# MCU.net
KiCad netlist of a schematic drawn in Altium Designer
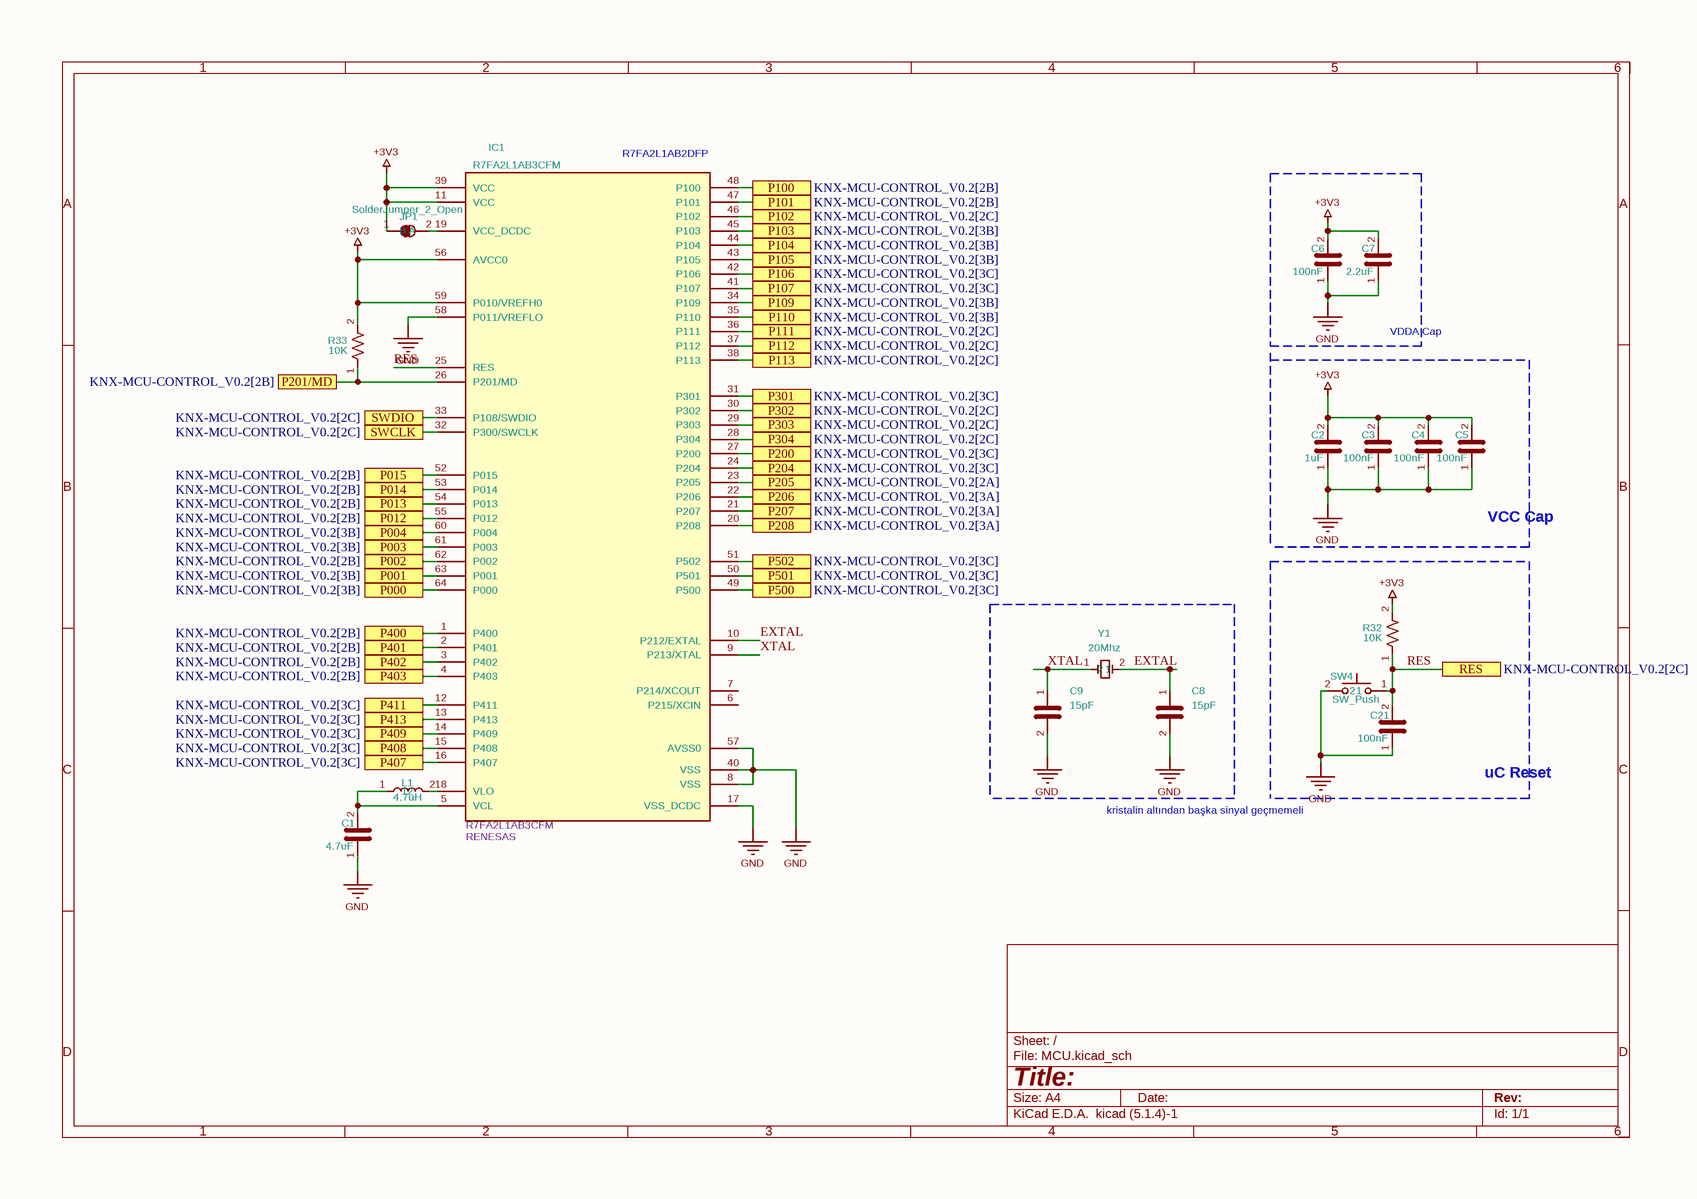
[diagram p0: MCU.SchDoc]

(export (version "E")
  (design (tool "Eeschema 10.0.6"))
  (components
    (comp (ref "C1")
      (value "4.7uF")
      (footprint "C_0603_1608Metric")
      (fields
        (field (name "MANUFACTURER PART NUMBER") "CL10B475KQ8NQNC")
        (field (name "MANUFACTURER") "Samsung Electro-Mechanics")
      )
      (libsource (lib "*") (part "C_3"))
    )
    (comp (ref "C2")
      (value "1uF")
      (footprint "C_0603_1608Metric")
      (fields
        (field (name "MANUFACTURER PART NUMBER") "CL10B105KP8NNNC")
        (field (name "MANUFACTURER") "Samsung Electro-Mechanics")
      )
      (libsource (lib "*") (part "C_3"))
    )
    (comp (ref "C3")
      (value "100nF")
      (footprint "C_0603_1608Metric")
      (fields
        (field (name "MANUFACTURER PART NUMBER") "CC0603KRX7R9BB104")
        (field (name "MANUFACTURER") "YAGEO")
      )
      (libsource (lib "*") (part "C_3"))
    )
    (comp (ref "C4")
      (value "100nF")
      (footprint "C_0603_1608Metric")
      (fields
        (field (name "MANUFACTURER PART NUMBER") "CC0603KRX7R9BB104")
        (field (name "MANUFACTURER") "YAGEO")
      )
      (libsource (lib "*") (part "C_3"))
    )
    (comp (ref "C5")
      (value "100nF")
      (footprint "C_0603_1608Metric")
      (fields
        (field (name "MANUFACTURER PART NUMBER") "CC0603KRX7R9BB104")
        (field (name "MANUFACTURER") "YAGEO")
      )
      (libsource (lib "*") (part "C_3"))
    )
    (comp (ref "C6")
      (value "100nF")
      (footprint "C_0603_1608Metric")
      (fields
        (field (name "MANUFACTURER PART NUMBER") "CC0603KRX7R9BB104")
        (field (name "MANUFACTURER") "YAGEO")
      )
      (libsource (lib "*") (part "C_3"))
    )
    (comp (ref "C7")
      (value "2.2uF")
      (footprint "C_0603_1608Metric")
      (fields
        (field (name "MANUFACTURER PART NUMBER") "CL10B225KP8NNNC")
        (field (name "MANUFACTURER") "Samsung Electro-Mechanics")
      )
      (libsource (lib "*") (part "C_3"))
    )
    (comp (ref "C8")
      (value "15pF")
      (footprint "C_0603_1608Metric")
      (fields
        (field (name "MANUFACTURER PART NUMBER") "CL10C150JB8NNNC")
        (field (name "MANUFACTURER") "Samsung Electro-Mechanics")
      )
      (libsource (lib "SparkFun-Capacitor") (part "20pF_0402_50V_5%"))
    )
    (comp (ref "C9")
      (value "15pF")
      (footprint "C_0603_1608Metric")
      (fields
        (field (name "MANUFACTURER PART NUMBER") "CL10C150JB8NNNC")
        (field (name "MANUFACTURER") "Samsung Electro-Mechanics")
      )
      (libsource (lib "SparkFun-Capacitor") (part "20pF_0402_50V_5%"))
    )
    (comp (ref "C21")
      (value "100nF")
      (footprint "C_0603_1608Metric")
      (fields
        (field (name "MANUFACTURER PART NUMBER") "CC0603KRX7R9BB104")
        (field (name "MANUFACTURER") "YAGEO")
      )
      (libsource (lib "*") (part "C_3"))
    )
    (comp (ref "IC1")
      (value "R7FA2L1AB3CFM")
      (footprint "LQFP-64_10x10mm_P0.5mm")
      (fields
        (field (name "MANUFACTURER PART NUMBER") "R7FA2L1AB3CFM")
        (field (name "MANUFACTURER") "RENESAS")
      )
      (libsource (lib "Me_Library") (part "R7FA2L1AB3CFM"))
    )
    (comp (ref "JP1")
      (value "SolderJumper_2_Open")
      (footprint "SolderJumper-2_P1.3mm_Open_TrianglePad1.0x1.5mm")
      (libsource (lib "Jumper") (part "SolderJumper_2_Open"))
    )
    (comp (ref "L1")
      (value "4.7uH")
      (footprint "L_APV_ANR5012")
      (fields (field (name "MANUFACTURER") "VIKING") (field (name "MANUFACTURER PART NUMBER") "PCD0302MT4R7"))
      (libsource (lib "Device") (part "L"))
    )
    (comp (ref "R32")
      (value "10K")
      (footprint "R_0603_1608Metric")
      (fields (field (name "MANUFACTURER PART NUMBER") "FRC0603J103TS") (field (name "MANUFACTURER") "FOJAN"))
      (libsource (lib "Device") (part "R_US"))
    )
    (comp (ref "R33")
      (value "10K")
      (footprint "R_0603_1608Metric")
      (fields (field (name "MANUFACTURER PART NUMBER") "FRC0603J103TS") (field (name "MANUFACTURER") "FOJAN"))
      (libsource (lib "Device") (part "R_US"))
    )
    (comp (ref "SW4")
      (value "SW_Push")
      (footprint "SW_SPST_CK_RS282G05A3")
      (description "SWITCH TACTILE SPST 250gf SMD")
      (fields
        (field (name "MANUFACTURER PART NUMBER") "HX 3x6x2.5A-2.5N")
        (field (name "MANUFACTURER") "hanxia")
      )
      (libsource (lib "Switch") (part "SW_Push"))
    )
    (comp (ref "Y1")
      (value "20Mhz")
      (footprint "Crystal_SMD_SeikoEpson_FA238-4Pin_3.2x2.5mm")
      (fields
        (field (name "MANUFACTURER PART NUMBER") "FL3P2X2P5SSC")
        (field (name "MANUFACTURER") "RALTRON")
      )
      (libsource (lib "SparkFun-Clock") (part "Crystal"))
    )
  )
  (nets
    (net (code "1") (name "+3V3") (class "Default")
      (node (ref "C2") (pin "2") (pinfunction "2_2") (pintype "passive"))
      (node (ref "C3") (pin "2") (pinfunction "2_2") (pintype "passive"))
      (node (ref "C4") (pin "2") (pinfunction "2_2") (pintype "passive"))
      (node (ref "C5") (pin "2") (pinfunction "2_2") (pintype "passive"))
      (node (ref "C6") (pin "2") (pinfunction "2_2") (pintype "passive"))
      (node (ref "C7") (pin "2") (pinfunction "2_2") (pintype "passive"))
      (node (ref "IC1") (pin "11") (pinfunction "VCC_11") (pintype "passive"))
      (node (ref "IC1") (pin "39") (pinfunction "VCC_39") (pintype "passive"))
      (node (ref "IC1") (pin "56") (pinfunction "AVCC0_56") (pintype "passive"))
      (node (ref "IC1") (pin "59") (pinfunction "P010/VREFH0_59") (pintype "passive"))
      (node (ref "JP1") (pin "1") (pinfunction "A_1") (pintype "passive"))
      (node (ref "R32") (pin "2") (pinfunction "2_2") (pintype "passive"))
      (node (ref "R33") (pin "2") (pinfunction "2_2") (pintype "passive"))
    )
    (net (code "2") (name "/EXTAL") (class "Default")
      (node (ref "C8") (pin "1") (pinfunction "1_1") (pintype "passive"))
      (node (ref "IC1") (pin "10") (pinfunction "P212/EXTAL_10") (pintype "passive"))
      (node (ref "Y1") (pin "2") (pinfunction "2_2") (pintype "passive"))
    )
    (net (code "3") (name "/P000") (class "Default")
      (node (ref "IC1") (pin "64") (pinfunction "P000_64") (pintype "passive"))
    )
    (net (code "4") (name "/P001") (class "Default")
      (node (ref "IC1") (pin "63") (pinfunction "P001_63") (pintype "passive"))
    )
    (net (code "5") (name "/P002") (class "Default")
      (node (ref "IC1") (pin "62") (pinfunction "P002_62") (pintype "passive"))
    )
    (net (code "6") (name "/P003") (class "Default")
      (node (ref "IC1") (pin "61") (pinfunction "P003_61") (pintype "passive"))
    )
    (net (code "7") (name "/P004") (class "Default")
      (node (ref "IC1") (pin "60") (pinfunction "P004_60") (pintype "passive"))
    )
    (net (code "8") (name "/P012") (class "Default")
      (node (ref "IC1") (pin "55") (pinfunction "P012_55") (pintype "passive"))
    )
    (net (code "9") (name "/P013") (class "Default")
      (node (ref "IC1") (pin "54") (pinfunction "P013_54") (pintype "passive"))
    )
    (net (code "10") (name "/P014") (class "Default")
      (node (ref "IC1") (pin "53") (pinfunction "P014_53") (pintype "passive"))
    )
    (net (code "11") (name "/P015") (class "Default")
      (node (ref "IC1") (pin "52") (pinfunction "P015_52") (pintype "passive"))
    )
    (net (code "12") (name "/P100") (class "Default")
      (node (ref "IC1") (pin "48") (pinfunction "P100_48") (pintype "passive"))
    )
    (net (code "13") (name "/P101") (class "Default")
      (node (ref "IC1") (pin "47") (pinfunction "P101_47") (pintype "passive"))
    )
    (net (code "14") (name "/P102") (class "Default")
      (node (ref "IC1") (pin "46") (pinfunction "P102_46") (pintype "passive"))
    )
    (net (code "15") (name "/P103") (class "Default")
      (node (ref "IC1") (pin "45") (pinfunction "P103_45") (pintype "passive"))
    )
    (net (code "16") (name "/P104") (class "Default")
      (node (ref "IC1") (pin "44") (pinfunction "P104_44") (pintype "passive"))
    )
    (net (code "17") (name "/P105") (class "Default")
      (node (ref "IC1") (pin "43") (pinfunction "P105_43") (pintype "passive"))
    )
    (net (code "18") (name "/P106") (class "Default")
      (node (ref "IC1") (pin "42") (pinfunction "P106_42") (pintype "passive"))
    )
    (net (code "19") (name "/P107") (class "Default")
      (node (ref "IC1") (pin "41") (pinfunction "P107_41") (pintype "passive"))
    )
    (net (code "20") (name "/P109") (class "Default")
      (node (ref "IC1") (pin "34") (pinfunction "P109_34") (pintype "passive"))
    )
    (net (code "21") (name "/P110") (class "Default")
      (node (ref "IC1") (pin "35") (pinfunction "P110_35") (pintype "passive"))
    )
    (net (code "22") (name "/P111") (class "Default")
      (node (ref "IC1") (pin "36") (pinfunction "P111_36") (pintype "passive"))
    )
    (net (code "23") (name "/P112") (class "Default")
      (node (ref "IC1") (pin "37") (pinfunction "P112_37") (pintype "passive"))
    )
    (net (code "24") (name "/P113") (class "Default")
      (node (ref "IC1") (pin "38") (pinfunction "P113_38") (pintype "passive"))
    )
    (net (code "25") (name "/P200") (class "Default")
      (node (ref "IC1") (pin "27") (pinfunction "P200_27") (pintype "passive"))
    )
    (net (code "26") (name "/P201{slash}MD") (class "Default")
      (node (ref "IC1") (pin "26") (pinfunction "P201/MD_26") (pintype "passive"))
      (node (ref "R33") (pin "1") (pinfunction "1_1") (pintype "passive"))
    )
    (net (code "27") (name "/P204") (class "Default")
      (node (ref "IC1") (pin "24") (pinfunction "P204_24") (pintype "passive"))
    )
    (net (code "28") (name "/P205") (class "Default")
      (node (ref "IC1") (pin "23") (pinfunction "P205_23") (pintype "passive"))
    )
    (net (code "29") (name "/P206") (class "Default")
      (node (ref "IC1") (pin "22") (pinfunction "P206_22") (pintype "passive"))
    )
    (net (code "30") (name "/P207") (class "Default")
      (node (ref "IC1") (pin "21") (pinfunction "P207_21") (pintype "passive"))
    )
    (net (code "31") (name "/P208") (class "Default")
      (node (ref "IC1") (pin "20") (pinfunction "P208_20") (pintype "passive"))
    )
    (net (code "32") (name "/P301") (class "Default")
      (node (ref "IC1") (pin "31") (pinfunction "P301_31") (pintype "passive"))
    )
    (net (code "33") (name "/P302") (class "Default")
      (node (ref "IC1") (pin "30") (pinfunction "P302_30") (pintype "passive"))
    )
    (net (code "34") (name "/P303") (class "Default")
      (node (ref "IC1") (pin "29") (pinfunction "P303_29") (pintype "passive"))
    )
    (net (code "35") (name "/P304") (class "Default")
      (node (ref "IC1") (pin "28") (pinfunction "P304_28") (pintype "passive"))
    )
    (net (code "36") (name "/P400") (class "Default")
      (node (ref "IC1") (pin "1") (pinfunction "P400_1") (pintype "passive"))
    )
    (net (code "37") (name "/P401") (class "Default")
      (node (ref "IC1") (pin "2") (pinfunction "P401_2") (pintype "passive"))
    )
    (net (code "38") (name "/P402") (class "Default")
      (node (ref "IC1") (pin "3") (pinfunction "P402_3") (pintype "passive"))
    )
    (net (code "39") (name "/P403") (class "Default")
      (node (ref "IC1") (pin "4") (pinfunction "P403_4") (pintype "passive"))
    )
    (net (code "40") (name "/P407") (class "Default")
      (node (ref "IC1") (pin "16") (pinfunction "P407_16") (pintype "passive"))
    )
    (net (code "41") (name "/P408") (class "Default")
      (node (ref "IC1") (pin "15") (pinfunction "P408_15") (pintype "passive"))
    )
    (net (code "42") (name "/P409") (class "Default")
      (node (ref "IC1") (pin "14") (pinfunction "P409_14") (pintype "passive"))
    )
    (net (code "43") (name "/P411") (class "Default")
      (node (ref "IC1") (pin "12") (pinfunction "P411_12") (pintype "passive"))
    )
    (net (code "44") (name "/P413") (class "Default")
      (node (ref "IC1") (pin "13") (pinfunction "P413_13") (pintype "passive"))
    )
    (net (code "45") (name "/P500") (class "Default")
      (node (ref "IC1") (pin "49") (pinfunction "P500_49") (pintype "passive"))
    )
    (net (code "46") (name "/P501") (class "Default")
      (node (ref "IC1") (pin "50") (pinfunction "P501_50") (pintype "passive"))
    )
    (net (code "47") (name "/P502") (class "Default")
      (node (ref "IC1") (pin "51") (pinfunction "P502_51") (pintype "passive"))
    )
    (net (code "48") (name "/RES") (class "Default")
      (node (ref "C21") (pin "2") (pinfunction "2_2") (pintype "passive"))
      (node (ref "IC1") (pin "25") (pinfunction "RES_25") (pintype "passive"))
      (node (ref "R32") (pin "1") (pinfunction "1_1") (pintype "passive"))
      (node (ref "SW4") (pin "1") (pinfunction "1_1") (pintype "passive"))
    )
    (net (code "49") (name "/SWCLK") (class "Default")
      (node (ref "IC1") (pin "32") (pinfunction "P300/SWCLK_32") (pintype "passive"))
    )
    (net (code "50") (name "/SWDIO") (class "Default")
      (node (ref "IC1") (pin "33") (pinfunction "P108/SWDIO_33") (pintype "passive"))
    )
    (net (code "51") (name "/XTAL") (class "Default")
      (node (ref "C9") (pin "1") (pinfunction "1_1") (pintype "passive"))
      (node (ref "IC1") (pin "9") (pinfunction "P213/XTAL_9") (pintype "passive"))
      (node (ref "Y1") (pin "1") (pinfunction "1_1") (pintype "passive"))
    )
    (net (code "52") (name "GND") (class "Default")
      (node (ref "C1") (pin "1") (pinfunction "1_1") (pintype "passive"))
      (node (ref "C2") (pin "1") (pinfunction "1_1") (pintype "passive"))
      (node (ref "C21") (pin "1") (pinfunction "1_1") (pintype "passive"))
      (node (ref "C3") (pin "1") (pinfunction "1_1") (pintype "passive"))
      (node (ref "C4") (pin "1") (pinfunction "1_1") (pintype "passive"))
      (node (ref "C5") (pin "1") (pinfunction "1_1") (pintype "passive"))
      (node (ref "C6") (pin "1") (pinfunction "1_1") (pintype "passive"))
      (node (ref "C7") (pin "1") (pinfunction "1_1") (pintype "passive"))
      (node (ref "C8") (pin "2") (pinfunction "2_2") (pintype "passive"))
      (node (ref "C9") (pin "2") (pinfunction "2_2") (pintype "passive"))
      (node (ref "IC1") (pin "17") (pinfunction "VSS_DCDC_17") (pintype "passive"))
      (node (ref "IC1") (pin "40") (pinfunction "VSS_40") (pintype "passive"))
      (node (ref "IC1") (pin "57") (pinfunction "AVSS0_57") (pintype "passive"))
      (node (ref "IC1") (pin "58") (pinfunction "P011/VREFLO_58") (pintype "passive"))
      (node (ref "IC1") (pin "8") (pinfunction "VSS_8") (pintype "passive"))
      (node (ref "SW4") (pin "2") (pinfunction "2_2") (pintype "passive"))
    )
    (net (code "53") (name "Net-(IC1-VCC_DCDC)") (class "Default")
      (node (ref "IC1") (pin "19") (pinfunction "VCC_DCDC_19") (pintype "passive"))
      (node (ref "JP1") (pin "2") (pinfunction "B_2") (pintype "passive"))
    )
    (net (code "54") (name "Net-(IC1-VCL)") (class "Default")
      (node (ref "C1") (pin "2") (pinfunction "2_2") (pintype "passive"))
      (node (ref "IC1") (pin "5") (pinfunction "VCL_5") (pintype "passive"))
      (node (ref "L1") (pin "1") (pinfunction "1_1") (pintype "passive"))
    )
    (net (code "55") (name "Net-(IC1-VLO)") (class "Default")
      (node (ref "IC1") (pin "18") (pinfunction "VLO_18") (pintype "passive"))
      (node (ref "L1") (pin "2") (pinfunction "2_2") (pintype "passive"))
    )
    (net (code "56") (name "unconnected-(IC1-P214{slash}XCOUT-Pad7)") (class "Default")
      (node (ref "IC1") (pin "7") (pinfunction "P214/XCOUT_7") (pintype "passive"))
    )
    (net (code "57") (name "unconnected-(IC1-P215{slash}XCIN-Pad6)") (class "Default")
      (node (ref "IC1") (pin "6") (pinfunction "P215/XCIN_6") (pintype "passive"))
    )
  )
)
